# 03-power.net
KiCad netlist of a schematic drawn in Altium Designer
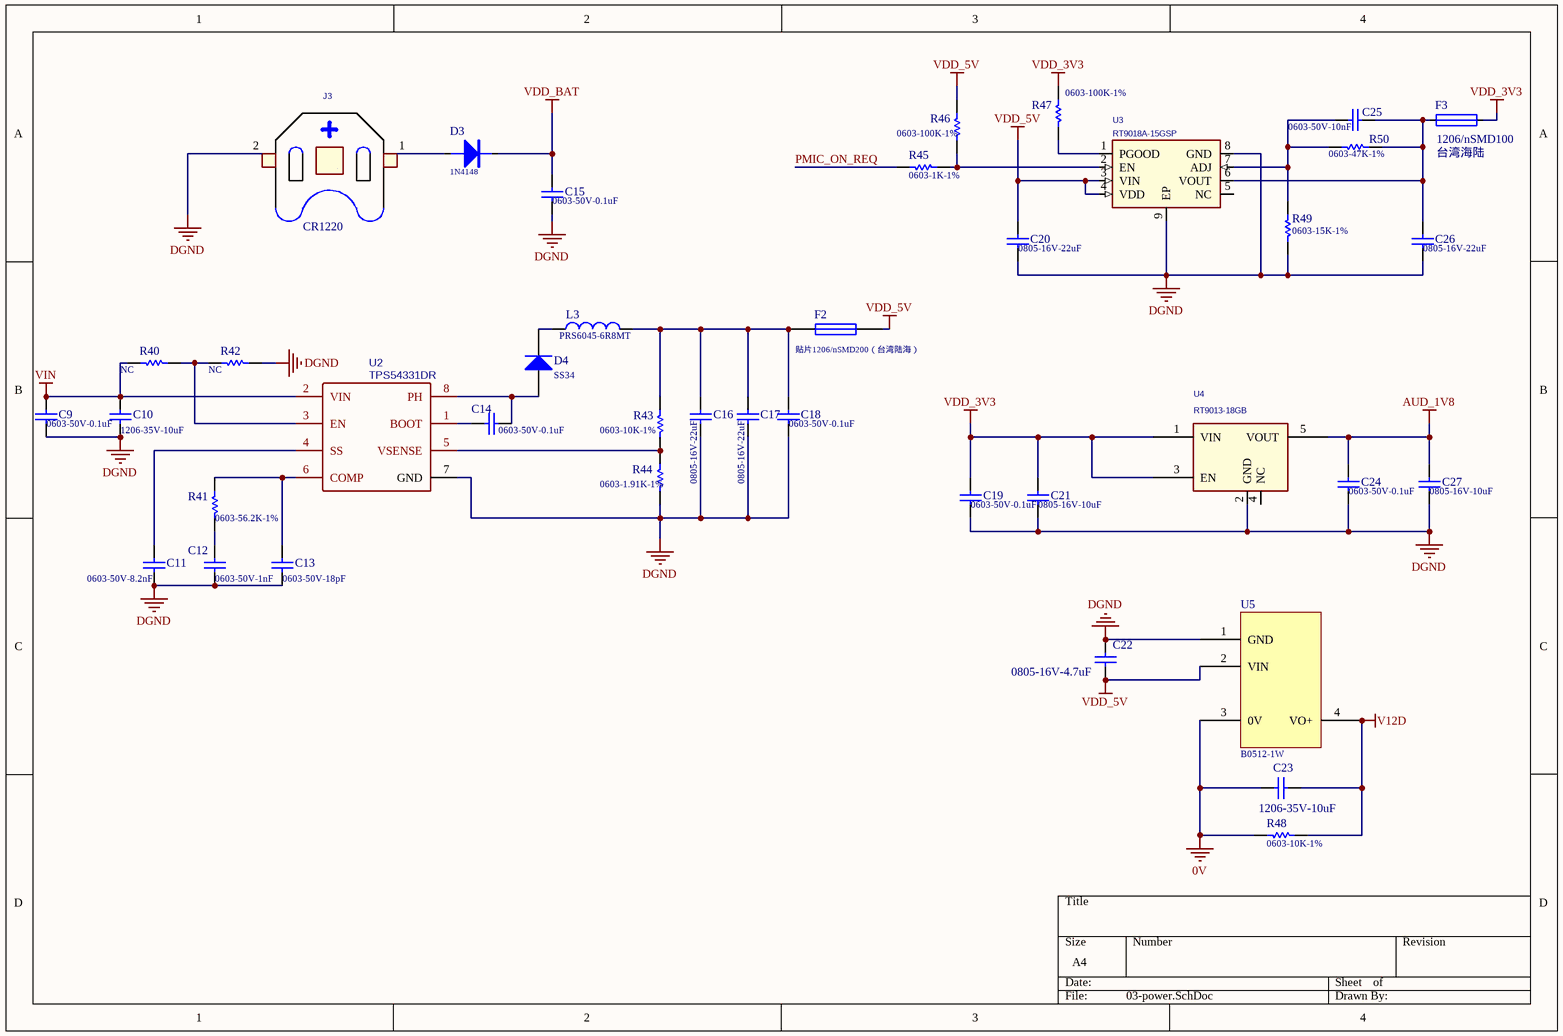
[diagram p0: 03-power.SchDoc]

(export (version "E")
  (design (tool "Eeschema 10.0.6"))
  (components
    (comp (ref "C9")
      (value "0603-50V-0.1uF")
      (footprint "0603C")
      (description "Capacitor")
      (fields (field (name "PUBLISHER") "Altium Limited"))
      (libsource (lib "Miscellaneous Devices") (part "Cap"))
    )
    (comp (ref "C10")
      (value "1206-35V-10uF")
      (footprint "1206C")
      (description "Capacitor")
      (fields (field (name "PUBLISHER") "Altium Limited"))
      (libsource (lib "Miscellaneous Devices") (part "Cap"))
    )
    (comp (ref "C11")
      (value "0603-50V-8.2nF")
      (footprint "0603C")
      (description "Capacitor")
      (fields (field (name "PUBLISHER") "Altium Limited"))
      (libsource (lib "Miscellaneous Devices") (part "Cap"))
    )
    (comp (ref "C12")
      (value "0603-50V-1nF")
      (footprint "0603C")
      (description "Capacitor")
      (fields (field (name "PUBLISHER") "Altium Limited"))
      (libsource (lib "Miscellaneous Devices") (part "Cap"))
    )
    (comp (ref "C13")
      (value "0603-50V-18pF")
      (footprint "0603C")
      (description "Capacitor")
      (fields (field (name "PUBLISHER") "Altium Limited"))
      (libsource (lib "Miscellaneous Devices") (part "Cap"))
    )
    (comp (ref "C14")
      (value "0603-50V-0.1uF")
      (footprint "0603C")
      (description "Capacitor")
      (fields (field (name "PUBLISHER") "Altium Limited"))
      (libsource (lib "Miscellaneous Devices") (part "Cap"))
    )
    (comp (ref "C15")
      (value "0603-50V-0.1uF")
      (footprint "0603C")
      (description "Capacitor")
      (fields (field (name "PUBLISHER") "Altium Limited"))
      (libsource (lib "Miscellaneous Devices") (part "Cap"))
    )
    (comp (ref "C16")
      (value "0805-16V-22uF")
      (footprint "0805C")
      (description "Capacitor")
      (fields (field (name "PUBLISHER") "Altium Limited"))
      (libsource (lib "Miscellaneous Devices") (part "Cap"))
    )
    (comp (ref "C17")
      (value "0805-16V-22uF")
      (footprint "0805C")
      (description "Capacitor")
      (fields (field (name "PUBLISHER") "Altium Limited"))
      (libsource (lib "Miscellaneous Devices") (part "Cap"))
    )
    (comp (ref "C18")
      (value "0603-50V-0.1uF")
      (footprint "0603C")
      (description "Capacitor")
      (fields (field (name "PUBLISHER") "Altium Limited"))
      (libsource (lib "Miscellaneous Devices") (part "Cap"))
    )
    (comp (ref "C19")
      (value "0603-50V-0.1uF")
      (footprint "0603C")
      (description "Capacitor")
      (fields (field (name "PUBLISHER") "Altium Limited"))
      (libsource (lib "Miscellaneous Devices") (part "Cap"))
    )
    (comp (ref "C20")
      (value "0805-16V-22uF")
      (footprint "0805C")
      (description "Capacitor")
      (fields (field (name "PUBLISHER") "Altium Limited"))
      (libsource (lib "Miscellaneous Devices") (part "Cap"))
    )
    (comp (ref "C21")
      (value "0805-16V-10uF")
      (footprint "0805C")
      (description "Capacitor")
      (fields (field (name "PUBLISHER") "Altium Limited"))
      (libsource (lib "Miscellaneous Devices") (part "Cap"))
    )
    (comp (ref "C22")
      (value "0805-16V-4.7uF")
      (footprint "1206C")
      (description "Capacitor")
      (fields (field (name "PUBLISHER") "Altium Limited"))
      (libsource (lib "Miscellaneous Devices") (part "Cap"))
    )
    (comp (ref "C23")
      (value "1206-35V-10uF")
      (footprint "1206C")
      (description "Capacitor")
      (fields (field (name "PUBLISHER") "Altium Limited"))
      (libsource (lib "Miscellaneous Devices") (part "Cap"))
    )
    (comp (ref "C24")
      (value "0603-50V-0.1uF")
      (footprint "0603C")
      (description "Capacitor")
      (fields (field (name "PUBLISHER") "Altium Limited"))
      (libsource (lib "Miscellaneous Devices") (part "Cap"))
    )
    (comp (ref "C25")
      (value "0603-50V-10nF")
      (footprint "0603C")
      (description "Capacitor")
      (fields (field (name "PUBLISHER") "Altium Limited"))
      (libsource (lib "Miscellaneous Devices") (part "Cap"))
    )
    (comp (ref "C26")
      (value "0805-16V-22uF")
      (footprint "0805C")
      (description "Capacitor")
      (fields (field (name "PUBLISHER") "Altium Limited"))
      (libsource (lib "Miscellaneous Devices") (part "Cap"))
    )
    (comp (ref "C27")
      (value "0805-16V-10uF")
      (footprint "0805C")
      (description "Capacitor")
      (fields (field (name "PUBLISHER") "Altium Limited"))
      (libsource (lib "Miscellaneous Devices") (part "Cap"))
    )
    (comp (ref "D3")
      (value "1N4148")
      (footprint "SOD-323")
      (description "Diode")
      (libsource (lib "*") (part "DIODE"))
    )
    (comp (ref "D4")
      (value "SS34")
      (footprint "SMA")
      (description "Silicon Switching Diode for High-Speed Switching")
      (fields (field (name "PUBLISHER") "Altium Limited"))
      (libsource (lib "Miscellaneous Devices") (part "Diode BAS16"))
    )
    (comp (ref "F2")
      (value "贴片1206/nSMD200（台湾陆海）")
      (footprint "1206F")
      (description "Fuse")
      (fields (field (name "PUBLISHER") "Altium Limited"))
      (libsource (lib "") (part "Fuse 1_1"))
    )
    (comp (ref "F3")
      (value "1206/nSMD100")
      (footprint "1206F")
      (description "Fuse")
      (fields (field (name "厂家") "台湾海陆") (field (name "PUBLISHER") "Altium Limited"))
      (libsource (lib "Miscellaneous Devices") (part "Fuse 1"))
    )
    (comp (ref "J3")
      (value "CR1220")
      (footprint "CR1220")
      (description "Connector,Battery Holder for 1225,Brown,SMD")
      (fields (field (name "MANUFACTURER") "Leyconn"))
      (libsource (lib "*") (part "BatteryHolder_1225"))
    )
    (comp (ref "L3")
      (value "PRS6045-6R8MT")
      (footprint "SCDS125T 12.5*12.5")
      (description "贴片功率电感")
      (fields (field (name "PUBLISHER") "Altium Limited"))
      (libsource (lib "Miscellaneous Devices") (part "Inductor"))
    )
    (comp (ref "R40")
      (value "NC")
      (footprint "0603R")
      (description "Resistor")
      (fields (field (name "PUBLISHER") "Altium Limited"))
      (libsource (lib "Miscellaneous Devices") (part "Res1"))
    )
    (comp (ref "R41")
      (value "0603-56.2K-1%")
      (footprint "0603R")
      (description "Resistor")
      (fields (field (name "PUBLISHER") "Altium Limited"))
      (libsource (lib "Miscellaneous Devices") (part "Res1"))
    )
    (comp (ref "R42")
      (value "NC")
      (footprint "0603R")
      (description "Resistor")
      (fields (field (name "PUBLISHER") "Altium Limited"))
      (libsource (lib "Miscellaneous Devices") (part "Res1"))
    )
    (comp (ref "R43")
      (value "0603-10K-1%")
      (footprint "0603R")
      (description "Resistor")
      (fields (field (name "PUBLISHER") "Altium Limited"))
      (libsource (lib "Miscellaneous Devices") (part "Res1"))
    )
    (comp (ref "R44")
      (value "0603-1.91K-1%")
      (footprint "0603R")
      (description "Resistor")
      (fields (field (name "PUBLISHER") "Altium Limited"))
      (libsource (lib "Miscellaneous Devices") (part "Res1"))
    )
    (comp (ref "R45")
      (value "0603-1K-1%")
      (footprint "0603R")
      (description "Resistor")
      (fields (field (name "PUBLISHER") "Altium Limited"))
      (libsource (lib "Miscellaneous Devices") (part "Res1"))
    )
    (comp (ref "R46")
      (value "0603-100K-1%")
      (footprint "0603R")
      (description "Resistor")
      (fields (field (name "PUBLISHER") "Altium Limited"))
      (libsource (lib "Miscellaneous Devices") (part "Res1"))
    )
    (comp (ref "R47")
      (value "0603-100K-1%")
      (footprint "0603R")
      (description "Resistor")
      (fields (field (name "PUBLISHER") "Altium Limited"))
      (libsource (lib "Miscellaneous Devices") (part "Res1"))
    )
    (comp (ref "R48")
      (value "0603-10K-1%")
      (footprint "0603R")
      (description "Resistor")
      (fields (field (name "PUBLISHER") "Altium Limited"))
      (libsource (lib "Miscellaneous Devices") (part "Res1"))
    )
    (comp (ref "R49")
      (value "0603-15K-1%")
      (footprint "0603R")
      (description "Resistor")
      (fields (field (name "PUBLISHER") "Altium Limited"))
      (libsource (lib "Miscellaneous Devices") (part "Res1"))
    )
    (comp (ref "R50")
      (value "0603-47K-1%")
      (footprint "0603R")
      (description "Resistor")
      (fields (field (name "PUBLISHER") "Altium Limited"))
      (libsource (lib "Miscellaneous Devices") (part "Res1"))
    )
    (comp (ref "U2")
      (value "TPS54331DR")
      (footprint "LC-SOIC-8_150mil")
      (fields (field (name "BOM_SUPPLIER PART") "C9865"))
      (libsource (lib "altium-import") (part "root_0__"))
    )
    (comp (ref "U3")
      (value "RT9018A-15GSP")
      (footprint "LC-SOP-8_EP_150mil")
      (description "IC, Maximum 3A, Ultra Low Dropout Regulator 8SOP")
      (fields (field (name "MANUFACTURER") "Richtek"))
      (libsource (lib "*") (part "RT9018B"))
    )
    (comp (ref "U4")
      (value "RT9013-18GB")
      (footprint "SOT-23-5")
      (description "IC, REG LDO 1.8V 0.5A SOT23-5")
      (fields (field (name "MANUFACTURER") "Richtek"))
      (libsource (lib "*") (part "RT9013-18GB"))
    )
    (comp (ref "U5")
      (value "B0512-1W")
      (footprint "DIP-11.6X6.0X10.16")
      (description "隔离电源")
      (libsource (lib "SCH-QQ") (part "F1212XT-1WR2"))
    )
  )
  (nets
    (net (code "1") (name "/PMIC_ON_REQ") (class "Default")
      (node (ref "R45") (pin "1") (pinfunction "1_1") (pintype "passive"))
    )
    (net (code "2") (name "0V") (class "Default")
      (node (ref "C23") (pin "2") (pinfunction "2_2") (pintype "passive"))
      (node (ref "R48") (pin "1") (pinfunction "1_1") (pintype "passive"))
      (node (ref "U5") (pin "3") (pinfunction "0V_3") (pintype "passive"))
    )
    (net (code "3") (name "AUD_1V8") (class "Default")
      (node (ref "C24") (pin "1") (pinfunction "1_1") (pintype "passive"))
      (node (ref "C27") (pin "1") (pinfunction "1_1") (pintype "passive"))
      (node (ref "U4") (pin "5") (pinfunction "VOUT_5") (pintype "passive"))
    )
    (net (code "4") (name "DGND") (class "Default")
      (node (ref "C10") (pin "2") (pinfunction "2_2") (pintype "passive"))
      (node (ref "C11") (pin "2") (pinfunction "2_2") (pintype "passive"))
      (node (ref "C12") (pin "2") (pinfunction "2_2") (pintype "passive"))
      (node (ref "C13") (pin "2") (pinfunction "2_2") (pintype "passive"))
      (node (ref "C15") (pin "2") (pinfunction "2_2") (pintype "passive"))
      (node (ref "C16") (pin "2") (pinfunction "2_2") (pintype "passive"))
      (node (ref "C17") (pin "2") (pinfunction "2_2") (pintype "passive"))
      (node (ref "C18") (pin "2") (pinfunction "2_2") (pintype "passive"))
      (node (ref "C19") (pin "2") (pinfunction "2_2") (pintype "passive"))
      (node (ref "C20") (pin "2") (pinfunction "2_2") (pintype "passive"))
      (node (ref "C21") (pin "2") (pinfunction "2_2") (pintype "passive"))
      (node (ref "C22") (pin "2") (pinfunction "2_2") (pintype "passive"))
      (node (ref "C24") (pin "2") (pinfunction "2_2") (pintype "passive"))
      (node (ref "C26") (pin "2") (pinfunction "2_2") (pintype "passive"))
      (node (ref "C27") (pin "2") (pinfunction "2_2") (pintype "passive"))
      (node (ref "C9") (pin "2") (pinfunction "2_2") (pintype "passive"))
      (node (ref "J3") (pin "2") (pinfunction "P2_2") (pintype "passive"))
      (node (ref "R42") (pin "2") (pinfunction "2_2") (pintype "passive"))
      (node (ref "R44") (pin "2") (pinfunction "2_2") (pintype "passive"))
      (node (ref "R49") (pin "1") (pinfunction "1_1") (pintype "passive"))
      (node (ref "U2") (pin "7") (pinfunction "GND_7") (pintype "passive"))
      (node (ref "U3") (pin "8") (pinfunction "GND_8") (pintype "power_in"))
      (node (ref "U3") (pin "9") (pinfunction "EP_9") (pintype "power_in"))
      (node (ref "U4") (pin "2") (pinfunction "GND_2") (pintype "passive"))
      (node (ref "U5") (pin "1") (pinfunction "GND_1") (pintype "passive"))
    )
    (net (code "5") (name "Net-(C12-Pad1)") (class "Default")
      (node (ref "C12") (pin "1") (pinfunction "1_1") (pintype "passive"))
      (node (ref "R41") (pin "2") (pinfunction "2_2") (pintype "passive"))
    )
    (net (code "6") (name "Net-(C16-Pad1)") (class "Default")
      (node (ref "C16") (pin "1") (pinfunction "1_1") (pintype "passive"))
      (node (ref "C17") (pin "1") (pinfunction "1_1") (pintype "passive"))
      (node (ref "C18") (pin "1") (pinfunction "1_1") (pintype "passive"))
      (node (ref "F2") (pin "1") (pinfunction "1_1") (pintype "passive"))
      (node (ref "L3") (pin "2") (pinfunction "2_2") (pintype "passive"))
      (node (ref "R43") (pin "1") (pinfunction "1_1") (pintype "passive"))
    )
    (net (code "7") (name "Net-(D4-A)") (class "Default")
      (node (ref "C14") (pin "1") (pinfunction "1_1") (pintype "passive"))
      (node (ref "D4") (pin "1") (pinfunction "A_1") (pintype "passive"))
      (node (ref "U2") (pin "8") (pinfunction "PH_8") (pintype "passive"))
    )
    (net (code "8") (name "Net-(D4-K)") (class "Default")
      (node (ref "D4") (pin "2") (pinfunction "K_2") (pintype "passive"))
      (node (ref "L3") (pin "1") (pinfunction "1_1") (pintype "passive"))
    )
    (net (code "9") (name "Net-(J3-P1)") (class "Default")
      (node (ref "D3") (pin "1") (pinfunction "1_1") (pintype "passive"))
      (node (ref "J3") (pin "1") (pinfunction "P1_1") (pintype "passive"))
    )
    (net (code "10") (name "Net-(U2-BOOT)") (class "Default")
      (node (ref "C14") (pin "2") (pinfunction "2_2") (pintype "passive"))
      (node (ref "U2") (pin "1") (pinfunction "BOOT_1") (pintype "passive"))
    )
    (net (code "11") (name "Net-(U2-COMP)") (class "Default")
      (node (ref "C13") (pin "1") (pinfunction "1_1") (pintype "passive"))
      (node (ref "R41") (pin "1") (pinfunction "1_1") (pintype "passive"))
      (node (ref "U2") (pin "6") (pinfunction "COMP_6") (pintype "passive"))
    )
    (net (code "12") (name "Net-(U2-EN)") (class "Default")
      (node (ref "R40") (pin "2") (pinfunction "2_2") (pintype "passive"))
      (node (ref "R42") (pin "1") (pinfunction "1_1") (pintype "passive"))
      (node (ref "U2") (pin "3") (pinfunction "EN_3") (pintype "passive"))
    )
    (net (code "13") (name "Net-(U2-SS)") (class "Default")
      (node (ref "C11") (pin "1") (pinfunction "1_1") (pintype "passive"))
      (node (ref "U2") (pin "4") (pinfunction "SS_4") (pintype "passive"))
    )
    (net (code "14") (name "Net-(U2-VSENSE)") (class "Default")
      (node (ref "R43") (pin "2") (pinfunction "2_2") (pintype "passive"))
      (node (ref "R44") (pin "1") (pinfunction "1_1") (pintype "passive"))
      (node (ref "U2") (pin "5") (pinfunction "VSENSE_5") (pintype "passive"))
    )
    (net (code "15") (name "Net-(U3-ADJ)") (class "Default")
      (node (ref "C25") (pin "1") (pinfunction "1_1") (pintype "passive"))
      (node (ref "R49") (pin "2") (pinfunction "2_2") (pintype "passive"))
      (node (ref "R50") (pin "1") (pinfunction "1_1") (pintype "passive"))
      (node (ref "U3") (pin "7") (pinfunction "ADJ_7") (pintype "input"))
    )
    (net (code "16") (name "Net-(U3-EN)") (class "Default")
      (node (ref "R45") (pin "2") (pinfunction "2_2") (pintype "passive"))
      (node (ref "R46") (pin "2") (pinfunction "2_2") (pintype "passive"))
      (node (ref "U3") (pin "2") (pinfunction "EN_2") (pintype "input"))
    )
    (net (code "17") (name "Net-(U3-PGOOD)") (class "Default")
      (node (ref "R47") (pin "2") (pinfunction "2_2") (pintype "passive"))
      (node (ref "U3") (pin "1") (pinfunction "PGOOD_1") (pintype "passive"))
    )
    (net (code "18") (name "Net-(U3-VOUT)") (class "Default")
      (node (ref "C25") (pin "2") (pinfunction "2_2") (pintype "passive"))
      (node (ref "C26") (pin "1") (pinfunction "1_1") (pintype "passive"))
      (node (ref "F3") (pin "2") (pinfunction "2_2") (pintype "passive"))
      (node (ref "R50") (pin "2") (pinfunction "2_2") (pintype "passive"))
      (node (ref "U3") (pin "6") (pinfunction "VOUT_6") (pintype "passive"))
    )
    (net (code "19") (name "V12D") (class "Default")
      (node (ref "C23") (pin "1") (pinfunction "1_1") (pintype "passive"))
      (node (ref "R48") (pin "2") (pinfunction "2_2") (pintype "passive"))
      (node (ref "U5") (pin "4") (pinfunction "VO+_4") (pintype "passive"))
    )
    (net (code "20") (name "VDD_3V3") (class "Default")
      (node (ref "C19") (pin "1") (pinfunction "1_1") (pintype "passive"))
      (node (ref "C21") (pin "1") (pinfunction "1_1") (pintype "passive"))
      (node (ref "F3") (pin "1") (pinfunction "1_1") (pintype "passive"))
      (node (ref "R47") (pin "1") (pinfunction "1_1") (pintype "passive"))
      (node (ref "U4") (pin "1") (pinfunction "VIN_1") (pintype "passive"))
      (node (ref "U4") (pin "3") (pinfunction "EN_3") (pintype "passive"))
    )
    (net (code "21") (name "VDD_5V") (class "Default")
      (node (ref "C20") (pin "1") (pinfunction "1_1") (pintype "passive"))
      (node (ref "C22") (pin "1") (pinfunction "1_1") (pintype "passive"))
      (node (ref "F2") (pin "2") (pinfunction "2_2") (pintype "passive"))
      (node (ref "R46") (pin "1") (pinfunction "1_1") (pintype "passive"))
      (node (ref "U3") (pin "3") (pinfunction "VIN_3") (pintype "input"))
      (node (ref "U3") (pin "4") (pinfunction "VDD_4") (pintype "input"))
      (node (ref "U5") (pin "2") (pinfunction "VIN_2") (pintype "passive"))
    )
    (net (code "22") (name "VDD_BAT") (class "Default")
      (node (ref "C15") (pin "1") (pinfunction "1_1") (pintype "passive"))
      (node (ref "D3") (pin "2") (pinfunction "2_2") (pintype "passive"))
    )
    (net (code "23") (name "VIN") (class "Default")
      (node (ref "C10") (pin "1") (pinfunction "1_1") (pintype "passive"))
      (node (ref "C9") (pin "1") (pinfunction "1_1") (pintype "passive"))
      (node (ref "R40") (pin "1") (pinfunction "1_1") (pintype "passive"))
      (node (ref "U2") (pin "2") (pinfunction "VIN_2") (pintype "passive"))
    )
    (net (code "24") (name "unconnected-(U3-NC-Pad5)") (class "Default")
      (node (ref "U3") (pin "5") (pinfunction "NC_5") (pintype "passive"))
    )
    (net (code "25") (name "unconnected-(U4-NC-Pad4)") (class "Default")
      (node (ref "U4") (pin "4") (pinfunction "NC_4") (pintype "passive"))
    )
  )
)
